# USB_Junctions.net
KiCad netlist of a schematic drawn in EAGLE
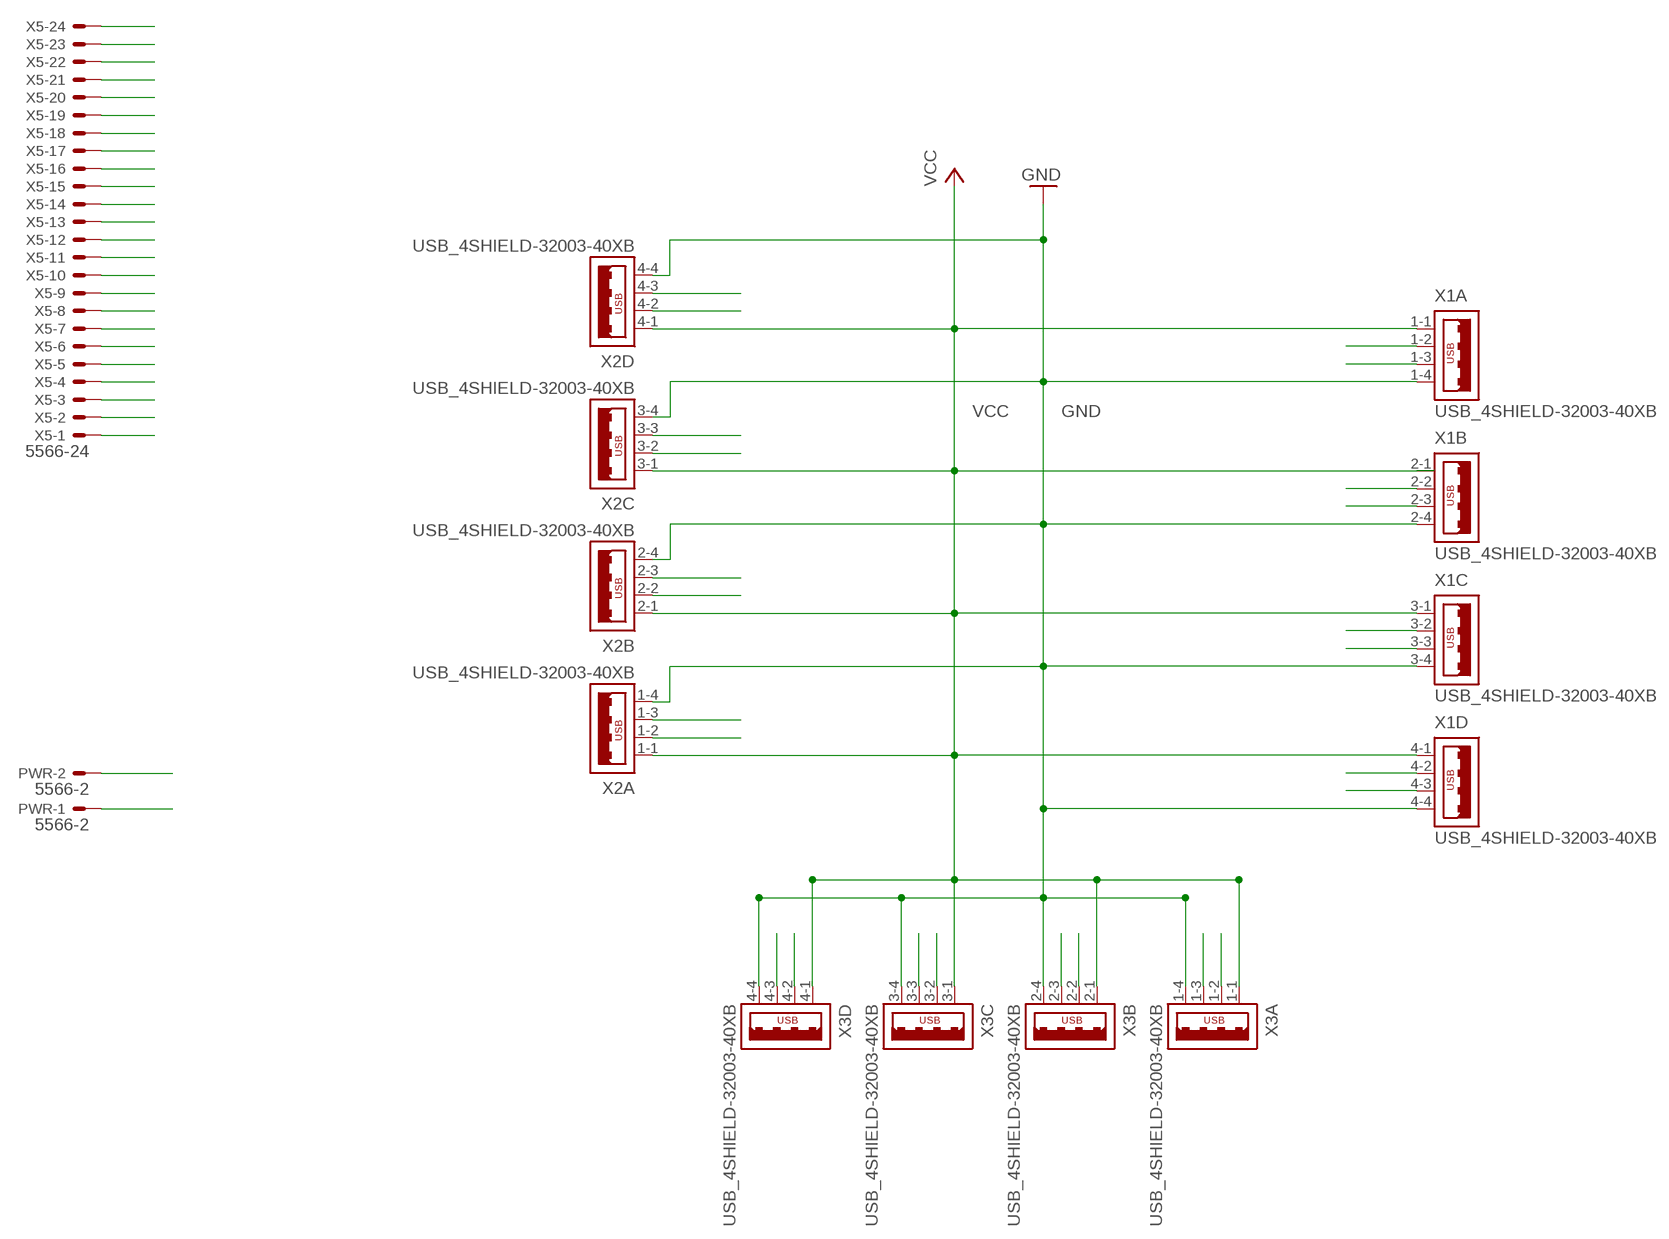
[diagram p0: schematic, sheet 1]

(export (version "E")
  (design (tool "Eeschema 10.0.6"))
  (components
    (comp (ref "PWR")
      (value "5566-2")
      (footprint "eagle-import:5566-2")
      (libsource (lib "eagle-import") (part "5566-2"))
    )
    (comp (ref "X1")
      (value "USB_4SHIELD-32003-40XB")
      (footprint "eagle-import:32003-40XB")
      (libsource (lib "eagle-import") (part "USB_4SHIELD-32003-40XB"))
    )
    (comp (ref "X2")
      (value "USB_4SHIELD-32003-40XB")
      (footprint "eagle-import:32003-40XB")
      (libsource (lib "eagle-import") (part "USB_4SHIELD-32003-40XB"))
    )
    (comp (ref "X3")
      (value "USB_4SHIELD-32003-40XB")
      (footprint "eagle-import:32003-40XB")
      (libsource (lib "eagle-import") (part "USB_4SHIELD-32003-40XB"))
    )
    (comp (ref "X5")
      (value "5566-24")
      (footprint "eagle-import:5566-24")
      (libsource (lib "eagle-import") (part "5566-24"))
    )
  )
  (nets
    (net (code "1") (name "/D1") (class "Default")
      (node (ref "X2") (pin "1-3") (pinfunction "3_1-3") (pintype "passive"))
      (node (ref "X5") (pin "1") (pinfunction "S_1") (pintype "passive"))
    )
    (net (code "2") (name "/D1-") (class "Default")
      (node (ref "X2") (pin "1-2") (pinfunction "2_1-2") (pintype "passive"))
      (node (ref "X5") (pin "2") (pinfunction "S_2") (pintype "passive"))
    )
    (net (code "3") (name "/D2") (class "Default")
      (node (ref "X2") (pin "2-3") (pinfunction "3_2-3") (pintype "passive"))
      (node (ref "X5") (pin "3") (pinfunction "S_3") (pintype "passive"))
    )
    (net (code "4") (name "/D2-") (class "Default")
      (node (ref "X2") (pin "2-2") (pinfunction "2_2-2") (pintype "passive"))
      (node (ref "X5") (pin "4") (pinfunction "S_4") (pintype "passive"))
    )
    (net (code "5") (name "/D3") (class "Default")
      (node (ref "X2") (pin "3-3") (pinfunction "3_3-3") (pintype "passive"))
      (node (ref "X5") (pin "5") (pinfunction "S_5") (pintype "passive"))
    )
    (net (code "6") (name "/D3-") (class "Default")
      (node (ref "X2") (pin "3-2") (pinfunction "2_3-2") (pintype "passive"))
      (node (ref "X5") (pin "6") (pinfunction "S_6") (pintype "passive"))
    )
    (net (code "7") (name "/D4") (class "Default")
      (node (ref "X2") (pin "4-3") (pinfunction "3_4-3") (pintype "passive"))
      (node (ref "X5") (pin "7") (pinfunction "S_7") (pintype "passive"))
    )
    (net (code "8") (name "/D4-") (class "Default")
      (node (ref "X2") (pin "4-2") (pinfunction "2_4-2") (pintype "passive"))
      (node (ref "X5") (pin "8") (pinfunction "S_8") (pintype "passive"))
    )
    (net (code "9") (name "/D5") (class "Default")
      (node (ref "X1") (pin "1-3") (pinfunction "3_1-3") (pintype "passive"))
      (node (ref "X5") (pin "9") (pinfunction "S_9") (pintype "passive"))
    )
    (net (code "10") (name "/D5-") (class "Default")
      (node (ref "X1") (pin "1-2") (pinfunction "2_1-2") (pintype "passive"))
      (node (ref "X5") (pin "10") (pinfunction "S_10") (pintype "passive"))
    )
    (net (code "11") (name "/D6") (class "Default")
      (node (ref "X1") (pin "2-3") (pinfunction "3_2-3") (pintype "passive"))
      (node (ref "X5") (pin "11") (pinfunction "S_11") (pintype "passive"))
    )
    (net (code "12") (name "/D6-") (class "Default")
      (node (ref "X1") (pin "2-2") (pinfunction "2_2-2") (pintype "passive"))
      (node (ref "X5") (pin "12") (pinfunction "S_12") (pintype "passive"))
    )
    (net (code "13") (name "/D7") (class "Default")
      (node (ref "X1") (pin "3-3") (pinfunction "3_3-3") (pintype "passive"))
      (node (ref "X5") (pin "13") (pinfunction "S_13") (pintype "passive"))
    )
    (net (code "14") (name "/D7-") (class "Default")
      (node (ref "X1") (pin "3-2") (pinfunction "2_3-2") (pintype "passive"))
      (node (ref "X5") (pin "14") (pinfunction "S_14") (pintype "passive"))
    )
    (net (code "15") (name "/D8") (class "Default")
      (node (ref "X1") (pin "4-3") (pinfunction "3_4-3") (pintype "passive"))
      (node (ref "X5") (pin "15") (pinfunction "S_15") (pintype "passive"))
    )
    (net (code "16") (name "/D8-") (class "Default")
      (node (ref "X1") (pin "4-2") (pinfunction "2_4-2") (pintype "passive"))
      (node (ref "X5") (pin "16") (pinfunction "S_16") (pintype "passive"))
    )
    (net (code "17") (name "/D9") (class "Default")
      (node (ref "X3") (pin "1-3") (pinfunction "3_1-3") (pintype "passive"))
      (node (ref "X5") (pin "17") (pinfunction "S_17") (pintype "passive"))
    )
    (net (code "18") (name "/D9-") (class "Default")
      (node (ref "X3") (pin "1-2") (pinfunction "2_1-2") (pintype "passive"))
      (node (ref "X5") (pin "18") (pinfunction "S_18") (pintype "passive"))
    )
    (net (code "19") (name "/D10") (class "Default")
      (node (ref "X3") (pin "2-3") (pinfunction "3_2-3") (pintype "passive"))
      (node (ref "X5") (pin "19") (pinfunction "S_19") (pintype "passive"))
    )
    (net (code "20") (name "/D10-") (class "Default")
      (node (ref "X3") (pin "2-2") (pinfunction "2_2-2") (pintype "passive"))
      (node (ref "X5") (pin "20") (pinfunction "S_20") (pintype "passive"))
    )
    (net (code "21") (name "/D11") (class "Default")
      (node (ref "X3") (pin "3-3") (pinfunction "3_3-3") (pintype "passive"))
      (node (ref "X5") (pin "21") (pinfunction "S_21") (pintype "passive"))
    )
    (net (code "22") (name "/D11-") (class "Default")
      (node (ref "X3") (pin "3-2") (pinfunction "2_3-2") (pintype "passive"))
      (node (ref "X5") (pin "22") (pinfunction "S_22") (pintype "passive"))
    )
    (net (code "23") (name "/D12") (class "Default")
      (node (ref "X3") (pin "4-3") (pinfunction "3_4-3") (pintype "passive"))
      (node (ref "X5") (pin "23") (pinfunction "S_23") (pintype "passive"))
    )
    (net (code "24") (name "/D12-") (class "Default")
      (node (ref "X3") (pin "4-2") (pinfunction "2_4-2") (pintype "passive"))
      (node (ref "X5") (pin "24") (pinfunction "S_24") (pintype "passive"))
    )
    (net (code "25") (name "GND") (class "Default")
      (node (ref "PWR") (pin "1") (pinfunction "S_1") (pintype "passive"))
      (node (ref "X1") (pin "1-4") (pinfunction "4_1-4") (pintype "passive"))
      (node (ref "X1") (pin "2-4") (pinfunction "4_2-4") (pintype "passive"))
      (node (ref "X1") (pin "3-4") (pinfunction "4_3-4") (pintype "passive"))
      (node (ref "X1") (pin "4-4") (pinfunction "4_4-4") (pintype "passive"))
      (node (ref "X2") (pin "1-4") (pinfunction "4_1-4") (pintype "passive"))
      (node (ref "X2") (pin "2-4") (pinfunction "4_2-4") (pintype "passive"))
      (node (ref "X2") (pin "3-4") (pinfunction "4_3-4") (pintype "passive"))
      (node (ref "X2") (pin "4-4") (pinfunction "4_4-4") (pintype "passive"))
      (node (ref "X3") (pin "1-4") (pinfunction "4_1-4") (pintype "passive"))
      (node (ref "X3") (pin "2-4") (pinfunction "4_2-4") (pintype "passive"))
      (node (ref "X3") (pin "3-4") (pinfunction "4_3-4") (pintype "passive"))
      (node (ref "X3") (pin "4-4") (pinfunction "4_4-4") (pintype "passive"))
    )
    (net (code "26") (name "VCC") (class "Default")
      (node (ref "PWR") (pin "2") (pinfunction "S_2") (pintype "passive"))
      (node (ref "X1") (pin "1-1") (pinfunction "1_1-1") (pintype "passive"))
      (node (ref "X1") (pin "2-1") (pinfunction "1_2-1") (pintype "passive"))
      (node (ref "X1") (pin "3-1") (pinfunction "1_3-1") (pintype "passive"))
      (node (ref "X1") (pin "4-1") (pinfunction "1_4-1") (pintype "passive"))
      (node (ref "X2") (pin "1-1") (pinfunction "1_1-1") (pintype "passive"))
      (node (ref "X2") (pin "2-1") (pinfunction "1_2-1") (pintype "passive"))
      (node (ref "X2") (pin "3-1") (pinfunction "1_3-1") (pintype "passive"))
      (node (ref "X2") (pin "4-1") (pinfunction "1_4-1") (pintype "passive"))
      (node (ref "X3") (pin "1-1") (pinfunction "1_1-1") (pintype "passive"))
      (node (ref "X3") (pin "2-1") (pinfunction "1_2-1") (pintype "passive"))
      (node (ref "X3") (pin "3-1") (pinfunction "1_3-1") (pintype "passive"))
      (node (ref "X3") (pin "4-1") (pinfunction "1_4-1") (pintype "passive"))
    )
  )
)
